# battery_monitor_6803-2_Rev2.net
KiCad netlist of a schematic drawn in EAGLE
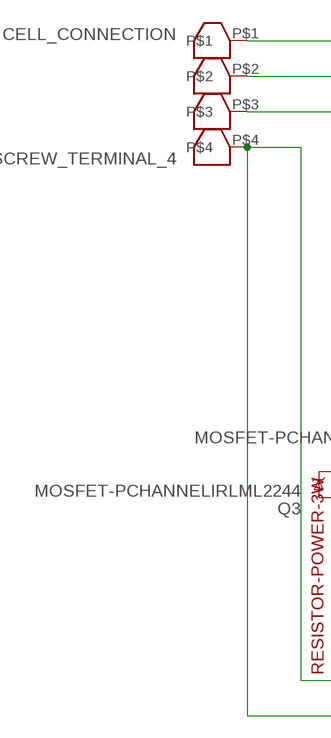
[diagram p0: schematic, sheet 1, part 1 of 2]
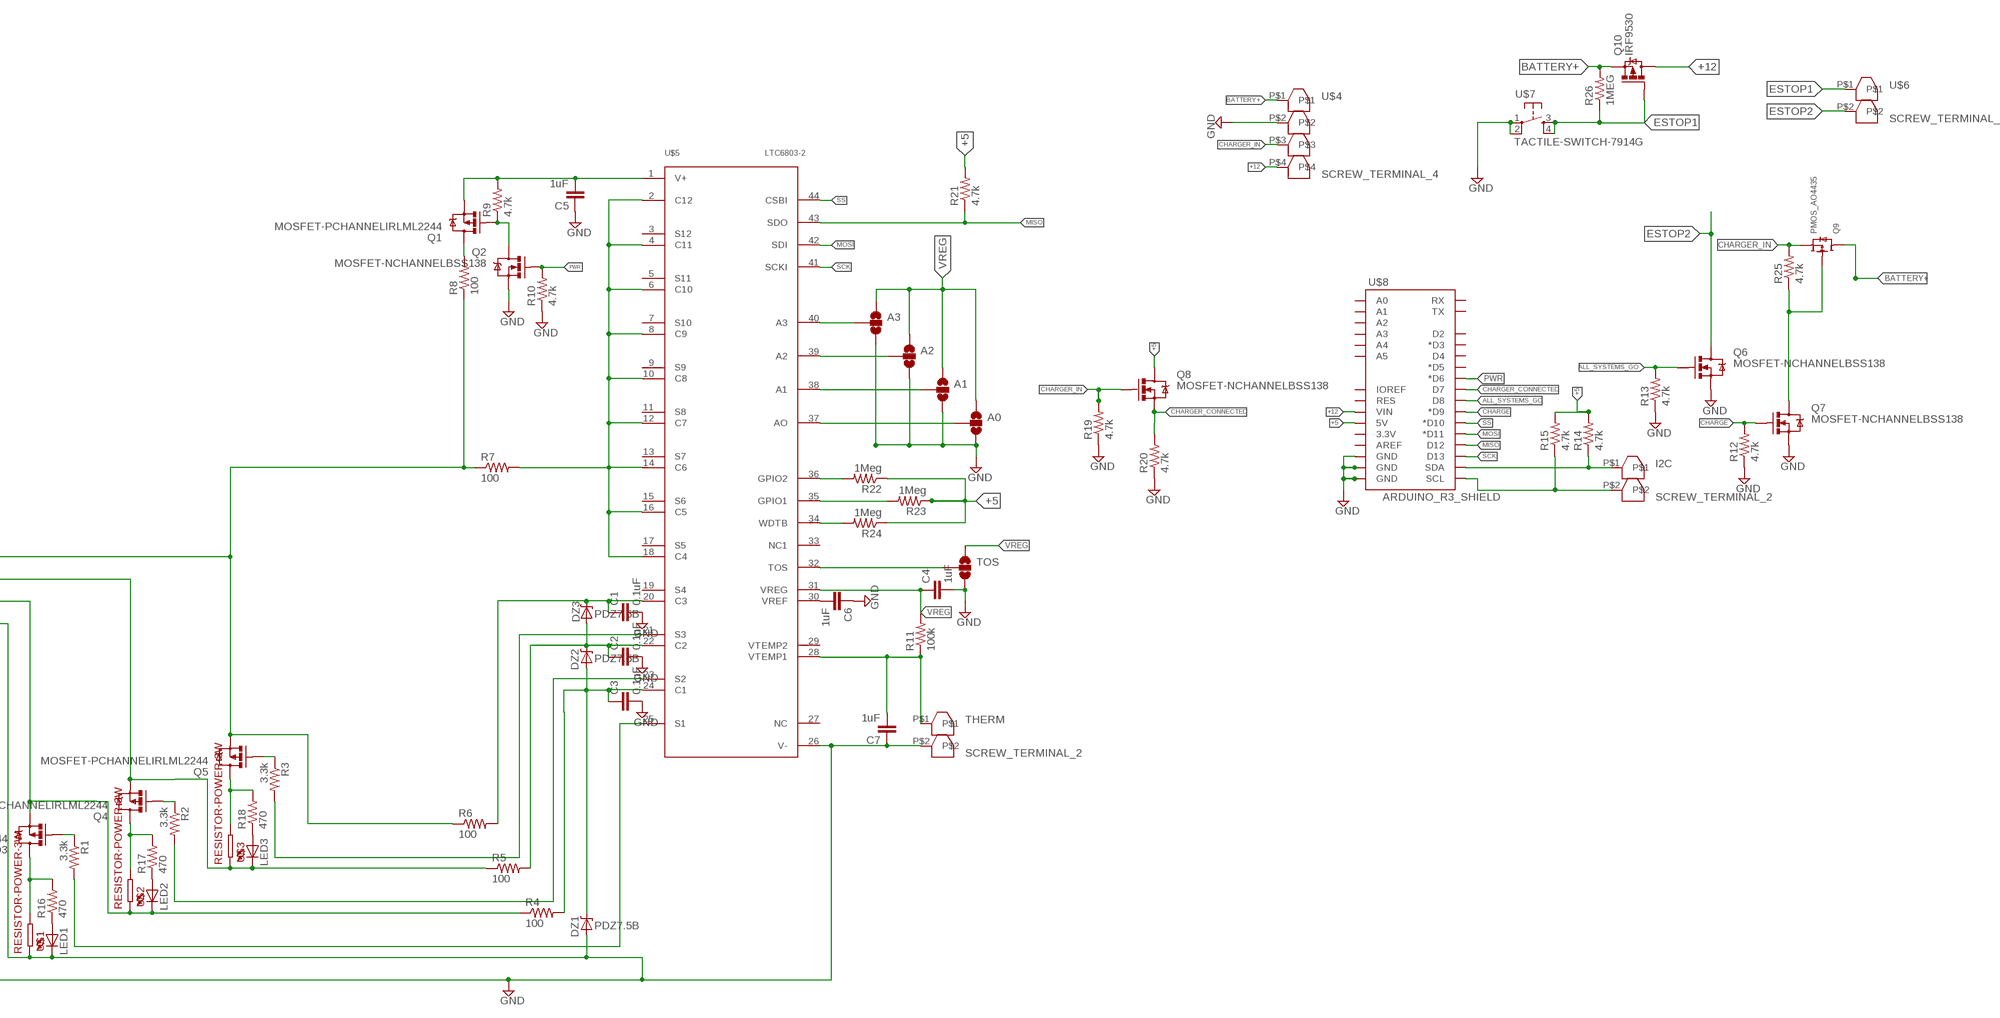
[diagram p1: schematic, sheet 1, part 2 of 2]

(export (version "E")
  (design (tool "Eeschema 10.0.6"))
  (components
    (comp (ref "A0")
      (value "SOLDERJUMPER_2WAYS")
      (footprint "eagle-import:SJ_3")
      (libsource (lib "eagle-import") (part "SOLDERJUMPER_2WAYS"))
    )
    (comp (ref "A1")
      (value "SOLDERJUMPER_2WAYS")
      (footprint "eagle-import:SJ_3")
      (libsource (lib "eagle-import") (part "SOLDERJUMPER_2WAYS"))
    )
    (comp (ref "A2")
      (value "SOLDERJUMPER_2WAYS")
      (footprint "eagle-import:SJ_3")
      (libsource (lib "eagle-import") (part "SOLDERJUMPER_2WAYS"))
    )
    (comp (ref "A3")
      (value "SOLDERJUMPER_2WAYS")
      (footprint "eagle-import:SJ_3")
      (libsource (lib "eagle-import") (part "SOLDERJUMPER_2WAYS"))
    )
    (comp (ref "C1")
      (value "0.1uF")
      (footprint "eagle-import:0603-CAP")
      (fields (field (name "MF") "AVX CORPORATION") (field (name "MPN") "0603YG104ZAT2A"))
      (libsource (lib "eagle-import") (part "0.1UF-100V-10%(0603)"))
    )
    (comp (ref "C2")
      (value "0.1uF")
      (footprint "eagle-import:0603-CAP")
      (fields (field (name "MF") "AVX CORPORATION") (field (name "MPN") "0603YG104ZAT2A"))
      (libsource (lib "eagle-import") (part "0.1UF-100V-10%(0603)"))
    )
    (comp (ref "C3")
      (value "0.1uF")
      (footprint "eagle-import:0603-CAP")
      (fields (field (name "MF") "AVX CORPORATION") (field (name "MPN") "0603YG104ZAT2A"))
      (libsource (lib "eagle-import") (part "0.1UF-100V-10%(0603)"))
    )
    (comp (ref "C4")
      (value "1uF")
      (footprint "eagle-import:0603-CAP")
      (fields (field (name "MPN") "C0603X5R0J105M030BC") (field (name "PROD_ID") "CAP-08390"))
      (libsource (lib "eagle-import") (part "0.1UF-100V-10%(0603)"))
    )
    (comp (ref "C5")
      (value "1uF")
      (footprint "eagle-import:0603-CAP")
      (fields (field (name "MPN") "C0603X5R0J105M030BC") (field (name "PROD_ID") "CAP-08390"))
      (libsource (lib "eagle-import") (part "0.1UF-100V-10%(0603)"))
    )
    (comp (ref "C6")
      (value "1uF")
      (footprint "eagle-import:0603-CAP")
      (fields (field (name "MPN") "C0603X5R0J105M030BC") (field (name "PROD_ID") "CAP-08390"))
      (libsource (lib "eagle-import") (part "0.1UF-100V-10%(0603)"))
    )
    (comp (ref "C7")
      (value "1uF")
      (footprint "eagle-import:0603-CAP")
      (fields (field (name "MPN") "C0603X5R0J105M030BC") (field (name "PROD_ID") "CAP-08390"))
      (libsource (lib "eagle-import") (part "0.1UF-100V-10%(0603)"))
    )
    (comp (ref "CELL_CONNECTION")
      (value "SCREW_TERMINAL_4")
      (footprint "eagle-import:SCREW_TERMINAL_4")
      (fields (field (name "MF") "TYCO ELECTRONICS") (field (name "MPN") "282834-4"))
      (libsource (lib "eagle-import") (part "SCREW_TERMINAL_4"))
    )
    (comp (ref "DZ1")
      (value "PDZ7.5B")
      (footprint "eagle-import:SOD-323")
      (fields (field (name "MPN") "PDZ7.5B,115"))
      (libsource (lib "eagle-import") (part "DIODE-ZENER-BZT52"))
    )
    (comp (ref "DZ2")
      (value "PDZ7.5B")
      (footprint "eagle-import:SOD-323")
      (fields (field (name "MPN") "PDZ7.5B,115"))
      (libsource (lib "eagle-import") (part "DIODE-ZENER-BZT52"))
    )
    (comp (ref "DZ3")
      (value "PDZ7.5B")
      (footprint "eagle-import:SOD-323")
      (fields (field (name "MPN") "PDZ7.5B,115"))
      (libsource (lib "eagle-import") (part "DIODE-ZENER-BZT52"))
    )
    (comp (ref "I2C")
      (value "SCREW_TERMINAL_2")
      (footprint "eagle-import:SCREW_TERMINAL_2")
      (fields (field (name "MF") "TYCO ELECTRONICS") (field (name "MPN") "282834-2"))
      (libsource (lib "eagle-import") (part "isaac1_SCREW_TERMINAL_2"))
    )
    (comp (ref "LED1")
      (value "LED0603")
      (footprint "eagle-import:LED-0603")
      (fields (field (name "MPN") "150060RS75000"))
      (libsource (lib "eagle-import") (part "LED0603"))
    )
    (comp (ref "LED2")
      (value "LED0603")
      (footprint "eagle-import:LED-0603")
      (fields (field (name "MPN") "150060RS75000"))
      (libsource (lib "eagle-import") (part "LED0603"))
    )
    (comp (ref "LED3")
      (value "LED0603")
      (footprint "eagle-import:LED-0603")
      (fields (field (name "MPN") "150060RS75000"))
      (libsource (lib "eagle-import") (part "LED0603"))
    )
    (comp (ref "Q1")
      (value "MOSFET-PCHANNELIRLML2244")
      (footprint "eagle-import:SOT23-3")
      (fields (field (name "MPN") "SI2369DS-T1-GE3"))
      (libsource (lib "eagle-import") (part "MOSFET-PCHANNELIRLML2244"))
    )
    (comp (ref "Q2")
      (value "MOSFET-NCHANNELBSS138")
      (footprint "eagle-import:SOT23")
      (fields (field (name "MPN") "IRLML0030TRPBF"))
      (libsource (lib "eagle-import") (part "MOSFET-NCHANNELBSS138"))
    )
    (comp (ref "Q3")
      (value "MOSFET-PCHANNELIRLML2244")
      (footprint "eagle-import:SOT23-3")
      (fields (field (name "MPN") "SI2369DS-T1-GE3"))
      (libsource (lib "eagle-import") (part "MOSFET-PCHANNELIRLML2244"))
    )
    (comp (ref "Q4")
      (value "MOSFET-PCHANNELIRLML2244")
      (footprint "eagle-import:SOT23-3")
      (fields (field (name "MPN") "SI2369DS-T1-GE3"))
      (libsource (lib "eagle-import") (part "MOSFET-PCHANNELIRLML2244"))
    )
    (comp (ref "Q5")
      (value "MOSFET-PCHANNELIRLML2244")
      (footprint "eagle-import:SOT23-3")
      (fields (field (name "MPN") "SI2369DS-T1-GE3"))
      (libsource (lib "eagle-import") (part "MOSFET-PCHANNELIRLML2244"))
    )
    (comp (ref "Q6")
      (value "MOSFET-NCHANNELBSS138")
      (footprint "eagle-import:SOT23")
      (fields (field (name "MPN") "IRLML0030TRPBF"))
      (libsource (lib "eagle-import") (part "MOSFET-NCHANNELBSS138"))
    )
    (comp (ref "Q7")
      (value "MOSFET-NCHANNELBSS138")
      (footprint "eagle-import:SOT23")
      (fields (field (name "MPN") "IRLML0030TRPBF"))
      (libsource (lib "eagle-import") (part "MOSFET-NCHANNELBSS138"))
    )
    (comp (ref "Q8")
      (value "MOSFET-NCHANNELBSS138")
      (footprint "eagle-import:SOT23")
      (fields (field (name "MPN") "IRLML0030TRPBF") (field (name "PROD_ID") "TRANS-00830"))
      (libsource (lib "eagle-import") (part "MOSFET-NCHANNELBSS138"))
    )
    (comp (ref "Q9")
      (value "PMOS_AO4435")
      (footprint "eagle-import:SOIC8")
      (fields (field (name "MPN") "SI9407BDY-T1-GE3"))
      (libsource (lib "eagle-import") (part "PMOS_AO4435"))
    )
    (comp (ref "Q10")
      (value "IRF9530")
      (footprint "eagle-import:TO220BV")
      (fields (field (name "MPN") "NTE2383"))
      (libsource (lib "eagle-import") (part "IRF9530"))
    )
    (comp (ref "R1")
      (value "3.3k")
      (footprint "eagle-import:0603-RES")
      (fields (field (name "MF") "VISHAY/DALE") (field (name "MPN") "CRCW06033K00FKEA"))
      (libsource (lib "eagle-import") (part "3.3KOHM1/10W1%(0603)"))
    )
    (comp (ref "R2")
      (value "3.3k")
      (footprint "eagle-import:0603-RES")
      (fields (field (name "MF") "VISHAY/DALE") (field (name "MPN") "CRCW06033K00FKEA"))
      (libsource (lib "eagle-import") (part "3.3KOHM1/10W1%(0603)"))
    )
    (comp (ref "R3")
      (value "3.3k")
      (footprint "eagle-import:0603-RES")
      (fields (field (name "MF") "VISHAY/DALE") (field (name "MPN") "CRCW06033K00FKEA"))
      (libsource (lib "eagle-import") (part "3.3KOHM1/10W1%(0603)"))
    )
    (comp (ref "R4")
      (value "100")
      (footprint "eagle-import:0603-RES")
      (fields (field (name "MPN") "ERJ-1GNF1000C"))
      (libsource (lib "eagle-import") (part "3.3KOHM1/10W1%(0603)"))
    )
    (comp (ref "R5")
      (value "100")
      (footprint "eagle-import:0603-RES")
      (fields (field (name "MPN") "ERJ-1GNF1000C"))
      (libsource (lib "eagle-import") (part "3.3KOHM1/10W1%(0603)"))
    )
    (comp (ref "R6")
      (value "100")
      (footprint "eagle-import:0603-RES")
      (fields (field (name "MPN") "ERJ-1GNF1000C"))
      (libsource (lib "eagle-import") (part "3.3KOHM1/10W1%(0603)"))
    )
    (comp (ref "R7")
      (value "100")
      (footprint "eagle-import:0603-RES")
      (fields (field (name "MPN") "ERJ-1GNF1000C"))
      (libsource (lib "eagle-import") (part "3.3KOHM1/10W1%(0603)"))
    )
    (comp (ref "R8")
      (value "100")
      (footprint "eagle-import:0603-RES")
      (fields (field (name "MPN") "ERJ-1GNF1000C"))
      (libsource (lib "eagle-import") (part "3.3KOHM1/10W1%(0603)"))
    )
    (comp (ref "R9")
      (value "4.7k")
      (footprint "eagle-import:0603-RES")
      (fields (field (name "MF") "VISHAY/DALE") (field (name "MPN") "CRCW06034K70FKEA"))
      (libsource (lib "eagle-import") (part "3.3KOHM1/10W1%(0603)"))
    )
    (comp (ref "R10")
      (value "4.7k")
      (footprint "eagle-import:0603-RES")
      (fields (field (name "MF") "VISHAY/DALE") (field (name "MPN") "CRCW06034K70FKEA"))
      (libsource (lib "eagle-import") (part "3.3KOHM1/10W1%(0603)"))
    )
    (comp (ref "R11")
      (value "100k")
      (footprint "eagle-import:0603-RES")
      (fields (field (name "MF") "FARNELL") (field (name "MPN") "MC0063W06035100K"))
      (libsource (lib "eagle-import") (part "3.3KOHM1/10W1%(0603)"))
    )
    (comp (ref "R12")
      (value "4.7k")
      (footprint "eagle-import:0603-RES")
      (fields (field (name "MF") "VISHAY/DALE") (field (name "MPN") "CRCW06034K70FKEA"))
      (libsource (lib "eagle-import") (part "3.3KOHM1/10W1%(0603)"))
    )
    (comp (ref "R13")
      (value "4.7k")
      (footprint "eagle-import:0603-RES")
      (fields (field (name "MF") "VISHAY/DALE") (field (name "MPN") "CRCW06034K70FKEA"))
      (libsource (lib "eagle-import") (part "3.3KOHM1/10W1%(0603)"))
    )
    (comp (ref "R14")
      (value "4.7k")
      (footprint "eagle-import:0603-RES")
      (fields (field (name "MF") "VISHAY/DALE") (field (name "MPN") "CRCW06034K70FKEA"))
      (libsource (lib "eagle-import") (part "3.3KOHM1/10W1%(0603)"))
    )
    (comp (ref "R15")
      (value "4.7k")
      (footprint "eagle-import:0603-RES")
      (fields (field (name "MF") "VISHAY/DALE") (field (name "MPN") "CRCW06034K70FKEA"))
      (libsource (lib "eagle-import") (part "3.3KOHM1/10W1%(0603)"))
    )
    (comp (ref "R16")
      (value "470")
      (footprint "eagle-import:0603-RES")
      (fields (field (name "MPN") "ERJ-P03F4700V") (field (name "PROD_ID") "RES-07851"))
      (libsource (lib "eagle-import") (part "3.3KOHM1/10W1%(0603)"))
    )
    (comp (ref "R17")
      (value "470")
      (footprint "eagle-import:0603-RES")
      (fields (field (name "MPN") "ERJ-P03F4700V") (field (name "PROD_ID") "RES-07851"))
      (libsource (lib "eagle-import") (part "3.3KOHM1/10W1%(0603)"))
    )
    (comp (ref "R18")
      (value "470")
      (footprint "eagle-import:0603-RES")
      (fields (field (name "MPN") "ERJ-P03F4700V") (field (name "PROD_ID") "RES-07851"))
      (libsource (lib "eagle-import") (part "3.3KOHM1/10W1%(0603)"))
    )
    (comp (ref "R19")
      (value "4.7k")
      (footprint "eagle-import:0603-RES")
      (fields
        (field (name "MF") "VISHAY/DALE")
        (field (name "MPN") "CRCW06034K70FKEA")
        (field (name "PROD_ID") "RES-07851")
      )
      (libsource (lib "eagle-import") (part "3.3KOHM1/10W1%(0603)"))
    )
    (comp (ref "R20")
      (value "4.7k")
      (footprint "eagle-import:0603-RES")
      (fields
        (field (name "MF") "VISHAY/DALE")
        (field (name "MPN") "CRCW06034K70FKEA")
        (field (name "PROD_ID") "RES-07851")
      )
      (libsource (lib "eagle-import") (part "3.3KOHM1/10W1%(0603)"))
    )
    (comp (ref "R21")
      (value "4.7k")
      (footprint "eagle-import:0603-RES")
      (fields
        (field (name "MF") "VISHAY/DALE")
        (field (name "MPN") "CRCW06034K70FKEA")
        (field (name "PROD_ID") "RES-07851")
      )
      (libsource (lib "eagle-import") (part "3.3KOHM1/10W1%(0603)"))
    )
    (comp (ref "R22")
      (value "1Meg")
      (footprint "eagle-import:0603-RES")
      (fields (field (name "MPN") "ERJ-3EKF1004V") (field (name "PROD_ID") "RES-07851"))
      (libsource (lib "eagle-import") (part "3.3KOHM1/10W1%(0603)"))
    )
    (comp (ref "R23")
      (value "1Meg")
      (footprint "eagle-import:0603-RES")
      (fields (field (name "MPN") "ERJ-3EKF1004V") (field (name "PROD_ID") "RES-07851"))
      (libsource (lib "eagle-import") (part "3.3KOHM1/10W1%(0603)"))
    )
    (comp (ref "R24")
      (value "1Meg")
      (footprint "eagle-import:0603-RES")
      (fields (field (name "MPN") "ERJ-3EKF1004V") (field (name "PROD_ID") "RES-07851"))
      (libsource (lib "eagle-import") (part "3.3KOHM1/10W1%(0603)"))
    )
    (comp (ref "R25")
      (value "4.7k")
      (footprint "eagle-import:0603-RES")
      (fields
        (field (name "MF") "VISHAY/DALE")
        (field (name "MPN") "CRCW06034K70FKEA")
        (field (name "PROD_ID") "RES-07851")
      )
      (libsource (lib "eagle-import") (part "3.3KOHM1/10W1%(0603)"))
    )
    (comp (ref "R26")
      (value "1MEG")
      (footprint "eagle-import:0603-RES")
      (fields (field (name "MPN") "ERJ-3EKF1004V"))
      (libsource (lib "eagle-import") (part "3.3KOHM1/10W1%(0603)"))
    )
    (comp (ref "THERM")
      (value "SCREW_TERMINAL_2")
      (footprint "eagle-import:SCREW_TERMINAL_2")
      (fields (field (name "MF") "TYCO ELECTRONICS") (field (name "MPN") "282834-2"))
      (libsource (lib "eagle-import") (part "isaac1_SCREW_TERMINAL_2"))
    )
    (comp (ref "TOS")
      (value "SOLDERJUMPER_2WAYS")
      (footprint "eagle-import:SJ_3")
      (libsource (lib "eagle-import") (part "SOLDERJUMPER_2WAYS"))
    )
    (comp (ref "U$1")
      (value "RESISTOR-POWER-3W")
      (footprint "eagle-import:RESISTOR-3W")
      (fields (field (name "MPN") "ERG-3SJ200"))
      (libsource (lib "eagle-import") (part "RESISTOR-POWER-3W"))
    )
    (comp (ref "U$2")
      (value "RESISTOR-POWER-3W")
      (footprint "eagle-import:RESISTOR-3W")
      (fields (field (name "MPN") "ERG-3SJ200"))
      (libsource (lib "eagle-import") (part "RESISTOR-POWER-3W"))
    )
    (comp (ref "U$3")
      (value "RESISTOR-POWER-3W")
      (footprint "eagle-import:RESISTOR-3W")
      (fields (field (name "MPN") "ERG-3SJ200"))
      (libsource (lib "eagle-import") (part "RESISTOR-POWER-3W"))
    )
    (comp (ref "U$4")
      (value "SCREW_TERMINAL_4")
      (footprint "eagle-import:SCREW_TERMINAL_4")
      (fields (field (name "MF") "TYCO ELECTRONICS") (field (name "MPN") "282834-4"))
      (libsource (lib "eagle-import") (part "SCREW_TERMINAL_4"))
    )
    (comp (ref "U$5")
      (value "LTC6803-2")
      (footprint "eagle-import:FSOP-44")
      (libsource (lib "eagle-import") (part "LTC6803-2"))
    )
    (comp (ref "U$6")
      (value "SCREW_TERMINAL_2")
      (footprint "eagle-import:SCREW_TERMINAL_2")
      (fields (field (name "MF") "TYCO ELECTRONICS") (field (name "MPN") "282834-2"))
      (libsource (lib "eagle-import") (part "SCREW_TERMINAL_2"))
    )
    (comp (ref "U$7")
      (value "TACTILE-SWITCH-7914G")
      (footprint "eagle-import:7914G")
      (fields (field (name "MF") "BOURNS, INC.") (field (name "MPN") "7914G-1-000E"))
      (libsource (lib "eagle-import") (part "TACTILE-SWITCH-7914G"))
    )
    (comp (ref "U$8")
      (value "ARDUINO_R3_SHIELD")
      (footprint "eagle-import:UNO_R3_SHIELD")
      (libsource (lib "eagle-import") (part "ARDUINO_R3_SHIELD"))
    )
  )
  (nets
    (net (code "1") (name "+5") (class "Default")
      (node (ref "Q8") (pin "3") (pinfunction "D_3") (pintype "passive"))
      (node (ref "R14") (pin "2") (pinfunction "2_2") (pintype "passive"))
      (node (ref "R15") (pin "2") (pinfunction "2_2") (pintype "passive"))
      (node (ref "R21") (pin "2") (pinfunction "2_2") (pintype "passive"))
      (node (ref "R22") (pin "1") (pinfunction "1_1") (pintype "passive"))
      (node (ref "R23") (pin "1") (pinfunction "1_1") (pintype "passive"))
      (node (ref "R24") (pin "1") (pinfunction "1_1") (pintype "passive"))
      (node (ref "U$8") (pin "5V") (pinfunction "5V_5V") (pintype "bidirectional"))
    )
    (net (code "2") (name "+12") (class "Default")
      (node (ref "Q10") (pin "D") (pinfunction "D_D") (pintype "passive"))
      (node (ref "U$4") (pin "P$4") (pinfunction "P$4_P$4") (pintype "bidirectional"))
      (node (ref "U$8") (pin "VIN") (pinfunction "VIN_VIN") (pintype "bidirectional"))
    )
    (net (code "3") (name "ALL_SYSTEMS_GO") (class "Default")
      (node (ref "Q6") (pin "1") (pinfunction "G_1") (pintype "passive"))
      (node (ref "R13") (pin "2") (pinfunction "2_2") (pintype "passive"))
      (node (ref "U$8") (pin "D8") (pinfunction "D8_D8") (pintype "bidirectional"))
    )
    (net (code "4") (name "BATTERY+") (class "Default")
      (node (ref "Q10") (pin "S") (pinfunction "S_S") (pintype "passive"))
      (node (ref "Q9") (pin "5") (pinfunction "DRAIN_5") (pintype "bidirectional"))
      (node (ref "Q9") (pin "6") (pinfunction "DRAIN_6") (pintype "bidirectional"))
      (node (ref "Q9") (pin "7") (pinfunction "DRAIN_7") (pintype "bidirectional"))
      (node (ref "Q9") (pin "8") (pinfunction "DRAIN_8") (pintype "bidirectional"))
      (node (ref "R26") (pin "2") (pinfunction "2_2") (pintype "passive"))
      (node (ref "U$4") (pin "P$1") (pinfunction "P$1_P$1") (pintype "bidirectional"))
    )
    (net (code "5") (name "CHARGE") (class "Default")
      (node (ref "Q7") (pin "1") (pinfunction "G_1") (pintype "passive"))
      (node (ref "R12") (pin "2") (pinfunction "2_2") (pintype "passive"))
      (node (ref "U$8") (pin "D9") (pinfunction "*D9_D9") (pintype "bidirectional"))
    )
    (net (code "6") (name "CHARGER_CONNECTED") (class "Default")
      (node (ref "Q8") (pin "2") (pinfunction "S_2") (pintype "passive"))
      (node (ref "R20") (pin "2") (pinfunction "2_2") (pintype "passive"))
      (node (ref "U$8") (pin "D7") (pinfunction "D7_D7") (pintype "bidirectional"))
    )
    (net (code "7") (name "CHARGER_IN") (class "Default")
      (node (ref "Q8") (pin "1") (pinfunction "G_1") (pintype "passive"))
      (node (ref "Q9") (pin "1") (pinfunction "SOURCE_1") (pintype "bidirectional"))
      (node (ref "Q9") (pin "2") (pinfunction "SOURCE_2") (pintype "bidirectional"))
      (node (ref "Q9") (pin "3") (pinfunction "SOURCE_3") (pintype "bidirectional"))
      (node (ref "R19") (pin "2") (pinfunction "2_2") (pintype "passive"))
      (node (ref "R25") (pin "2") (pinfunction "2_2") (pintype "passive"))
      (node (ref "U$4") (pin "P$3") (pinfunction "P$3_P$3") (pintype "bidirectional"))
    )
    (net (code "8") (name "ESTOP1") (class "Default")
      (node (ref "Q10") (pin "G") (pinfunction "G_G") (pintype "passive"))
      (node (ref "R26") (pin "1") (pinfunction "1_1") (pintype "passive"))
      (node (ref "U$6") (pin "P$1") (pinfunction "P$1_P$1") (pintype "bidirectional"))
      (node (ref "U$7") (pin "3") (pinfunction "3_3") (pintype "passive"))
      (node (ref "U$7") (pin "4") (pinfunction "4_4") (pintype "passive"))
    )
    (net (code "9") (name "ESTOP2") (class "Default")
      (node (ref "Q6") (pin "3") (pinfunction "D_3") (pintype "passive"))
      (node (ref "U$6") (pin "P$2") (pinfunction "P$2_P$2") (pintype "bidirectional"))
    )
    (net (code "10") (name "GND") (class "Default")
      (node (ref "A0") (pin "3") (pinfunction "3_3") (pintype "passive"))
      (node (ref "A1") (pin "3") (pinfunction "3_3") (pintype "passive"))
      (node (ref "A2") (pin "3") (pinfunction "3_3") (pintype "passive"))
      (node (ref "A3") (pin "3") (pinfunction "3_3") (pintype "passive"))
      (node (ref "C1") (pin "2") (pinfunction "2_2") (pintype "passive"))
      (node (ref "C2") (pin "2") (pinfunction "2_2") (pintype "passive"))
      (node (ref "C3") (pin "2") (pinfunction "2_2") (pintype "passive"))
      (node (ref "C4") (pin "2") (pinfunction "2_2") (pintype "passive"))
      (node (ref "C5") (pin "1") (pinfunction "1_1") (pintype "passive"))
      (node (ref "C6") (pin "1") (pinfunction "1_1") (pintype "passive"))
      (node (ref "C7") (pin "1") (pinfunction "1_1") (pintype "passive"))
      (node (ref "CELL_CONNECTION") (pin "P$4") (pinfunction "P$4_P$4") (pintype "bidirectional"))
      (node (ref "DZ1") (pin "2") (pinfunction "A_2") (pintype "passive"))
      (node (ref "LED1") (pin "C") (pinfunction "C_C") (pintype "passive"))
      (node (ref "Q2") (pin "2") (pinfunction "S_2") (pintype "passive"))
      (node (ref "Q6") (pin "2") (pinfunction "S_2") (pintype "passive"))
      (node (ref "Q7") (pin "2") (pinfunction "S_2") (pintype "passive"))
      (node (ref "R10") (pin "1") (pinfunction "1_1") (pintype "passive"))
      (node (ref "R12") (pin "1") (pinfunction "1_1") (pintype "passive"))
      (node (ref "R13") (pin "1") (pinfunction "1_1") (pintype "passive"))
      (node (ref "R19") (pin "1") (pinfunction "1_1") (pintype "passive"))
      (node (ref "R20") (pin "1") (pinfunction "1_1") (pintype "passive"))
      (node (ref "THERM") (pin "P$2") (pinfunction "P$2_P$2") (pintype "bidirectional"))
      (node (ref "TOS") (pin "3") (pinfunction "3_3") (pintype "passive"))
      (node (ref "U$1") (pin "P$2") (pinfunction "P$2_P$2") (pintype "bidirectional"))
      (node (ref "U$4") (pin "P$2") (pinfunction "P$2_P$2") (pintype "bidirectional"))
      (node (ref "U$5") (pin "26") (pinfunction "V-_26") (pintype "bidirectional"))
      (node (ref "U$7") (pin "1") (pinfunction "1_1") (pintype "passive"))
      (node (ref "U$7") (pin "2") (pinfunction "2_2") (pintype "passive"))
      (node (ref "U$8") (pin "GND@0") (pinfunction "GND_GND@0") (pintype "bidirectional"))
      (node (ref "U$8") (pin "GND@1") (pinfunction "GND_GND@1") (pintype "bidirectional"))
      (node (ref "U$8") (pin "GND@2") (pinfunction "GND_GND@2") (pintype "bidirectional"))
    )
    (net (code "11") (name "MISO") (class "Default")
      (node (ref "R21") (pin "1") (pinfunction "1_1") (pintype "passive"))
      (node (ref "U$5") (pin "43") (pinfunction "SDO_43") (pintype "bidirectional"))
      (node (ref "U$8") (pin "D12") (pinfunction "D12_D12") (pintype "bidirectional"))
    )
    (net (code "12") (name "MOSI") (class "Default")
      (node (ref "U$5") (pin "42") (pinfunction "SDI_42") (pintype "bidirectional"))
      (node (ref "U$8") (pin "D11") (pinfunction "*D11_D11") (pintype "bidirectional"))
    )
    (net (code "13") (name "Net-(DZ1-C)") (class "Default")
      (node (ref "C3") (pin "1") (pinfunction "1_1") (pintype "passive"))
      (node (ref "DZ1") (pin "1") (pinfunction "C_1") (pintype "passive"))
      (node (ref "DZ2") (pin "2") (pinfunction "A_2") (pintype "passive"))
      (node (ref "R4") (pin "2") (pinfunction "2_2") (pintype "passive"))
      (node (ref "U$5") (pin "24") (pinfunction "C1_24") (pintype "bidirectional"))
    )
    (net (code "14") (name "Net-(DZ2-C)") (class "Default")
      (node (ref "C2") (pin "1") (pinfunction "1_1") (pintype "passive"))
      (node (ref "DZ2") (pin "1") (pinfunction "C_1") (pintype "passive"))
      (node (ref "DZ3") (pin "2") (pinfunction "A_2") (pintype "passive"))
      (node (ref "R5") (pin "2") (pinfunction "2_2") (pintype "passive"))
      (node (ref "U$5") (pin "22") (pinfunction "C2_22") (pintype "bidirectional"))
    )
    (net (code "15") (name "Net-(DZ3-C)") (class "Default")
      (node (ref "C1") (pin "1") (pinfunction "1_1") (pintype "passive"))
      (node (ref "DZ3") (pin "1") (pinfunction "C_1") (pintype "passive"))
      (node (ref "R6") (pin "2") (pinfunction "2_2") (pintype "passive"))
      (node (ref "U$5") (pin "20") (pinfunction "C3_20") (pintype "bidirectional"))
    )
    (net (code "16") (name "Net-(I2C-PadP$1)") (class "Default")
      (node (ref "I2C") (pin "P$1") (pinfunction "P$1_P$1") (pintype "bidirectional"))
      (node (ref "R14") (pin "1") (pinfunction "1_1") (pintype "passive"))
      (node (ref "U$8") (pin "SDA") (pinfunction "SDA_SDA") (pintype "bidirectional"))
    )
    (net (code "17") (name "Net-(I2C-PadP$2)") (class "Default")
      (node (ref "I2C") (pin "P$2") (pinfunction "P$2_P$2") (pintype "bidirectional"))
      (node (ref "R15") (pin "1") (pinfunction "1_1") (pintype "passive"))
      (node (ref "U$8") (pin "SCL") (pinfunction "SCL_SCL") (pintype "bidirectional"))
    )
    (net (code "18") (name "Net-(LED1-PadA)") (class "Default")
      (node (ref "LED1") (pin "A") (pinfunction "A_A") (pintype "passive"))
      (node (ref "R16") (pin "1") (pinfunction "1_1") (pintype "passive"))
    )
    (net (code "19") (name "Net-(LED2-PadA)") (class "Default")
      (node (ref "LED2") (pin "A") (pinfunction "A_A") (pintype "passive"))
      (node (ref "R17") (pin "1") (pinfunction "1_1") (pintype "passive"))
    )
    (net (code "20") (name "Net-(LED3-PadA)") (class "Default")
      (node (ref "LED3") (pin "A") (pinfunction "A_A") (pintype "passive"))
      (node (ref "R18") (pin "1") (pinfunction "1_1") (pintype "passive"))
    )
    (net (code "21") (name "Net-(Q1-D)") (class "Default")
      (node (ref "Q1") (pin "3") (pinfunction "D_3") (pintype "passive"))
      (node (ref "R8") (pin "2") (pinfunction "2_2") (pintype "passive"))
    )
    (net (code "22") (name "Net-(Q1-G)") (class "Default")
      (node (ref "Q1") (pin "1") (pinfunction "G_1") (pintype "passive"))
      (node (ref "Q2") (pin "3") (pinfunction "D_3") (pintype "passive"))
      (node (ref "R9") (pin "1") (pinfunction "1_1") (pintype "passive"))
    )
    (net (code "23") (name "Net-(Q1-S)") (class "Default")
      (node (ref "C5") (pin "2") (pinfunction "2_2") (pintype "passive"))
      (node (ref "Q1") (pin "2") (pinfunction "S_2") (pintype "passive"))
      (node (ref "R9") (pin "2") (pinfunction "2_2") (pintype "passive"))
      (node (ref "U$5") (pin "1") (pinfunction "V+_1") (pintype "bidirectional"))
    )
    (net (code "24") (name "Net-(Q3-D)") (class "Default")
      (node (ref "Q3") (pin "3") (pinfunction "D_3") (pintype "passive"))
      (node (ref "R16") (pin "2") (pinfunction "2_2") (pintype "passive"))
      (node (ref "U$1") (pin "P$1") (pinfunction "P$1_P$1") (pintype "bidirectional"))
    )
    (net (code "25") (name "Net-(Q3-G)") (class "Default")
      (node (ref "Q3") (pin "1") (pinfunction "G_1") (pintype "passive"))
      (node (ref "R1") (pin "1") (pinfunction "1_1") (pintype "passive"))
    )
    (net (code "26") (name "Net-(Q3-S)") (class "Default")
      (node (ref "CELL_CONNECTION") (pin "P$3") (pinfunction "P$3_P$3") (pintype "bidirectional"))
      (node (ref "LED2") (pin "C") (pinfunction "C_C") (pintype "passive"))
      (node (ref "Q3") (pin "2") (pinfunction "S_2") (pintype "passive"))
      (node (ref "R4") (pin "1") (pinfunction "1_1") (pintype "passive"))
      (node (ref "U$2") (pin "P$2") (pinfunction "P$2_P$2") (pintype "bidirectional"))
    )
    (net (code "27") (name "Net-(Q4-D)") (class "Default")
      (node (ref "Q4") (pin "3") (pinfunction "D_3") (pintype "passive"))
      (node (ref "R17") (pin "2") (pinfunction "2_2") (pintype "passive"))
      (node (ref "U$2") (pin "P$1") (pinfunction "P$1_P$1") (pintype "bidirectional"))
    )
    (net (code "28") (name "Net-(Q4-G)") (class "Default")
      (node (ref "Q4") (pin "1") (pinfunction "G_1") (pintype "passive"))
      (node (ref "R2") (pin "1") (pinfunction "1_1") (pintype "passive"))
    )
    (net (code "29") (name "Net-(Q4-S)") (class "Default")
      (node (ref "CELL_CONNECTION") (pin "P$2") (pinfunction "P$2_P$2") (pintype "bidirectional"))
      (node (ref "LED3") (pin "C") (pinfunction "C_C") (pintype "passive"))
      (node (ref "Q4") (pin "2") (pinfunction "S_2") (pintype "passive"))
      (node (ref "R5") (pin "1") (pinfunction "1_1") (pintype "passive"))
      (node (ref "U$3") (pin "P$2") (pinfunction "P$2_P$2") (pintype "bidirectional"))
    )
    (net (code "30") (name "Net-(Q5-D)") (class "Default")
      (node (ref "Q5") (pin "3") (pinfunction "D_3") (pintype "passive"))
      (node (ref "R18") (pin "2") (pinfunction "2_2") (pintype "passive"))
      (node (ref "U$3") (pin "P$1") (pinfunction "P$1_P$1") (pintype "bidirectional"))
    )
    (net (code "31") (name "Net-(Q5-G)") (class "Default")
      (node (ref "Q5") (pin "1") (pinfunction "G_1") (pintype "passive"))
      (node (ref "R3") (pin "1") (pinfunction "1_1") (pintype "passive"))
    )
    (net (code "32") (name "Net-(Q5-S)") (class "Default")
      (node (ref "CELL_CONNECTION") (pin "P$1") (pinfunction "P$1_P$1") (pintype "bidirectional"))
      (node (ref "Q5") (pin "2") (pinfunction "S_2") (pintype "passive"))
      (node (ref "R6") (pin "1") (pinfunction "1_1") (pintype "passive"))
      (node (ref "R7") (pin "1") (pinfunction "1_1") (pintype "passive"))
      (node (ref "R8") (pin "1") (pinfunction "1_1") (pintype "passive"))
    )
    (net (code "33") (name "Net-(Q7-D)") (class "Default")
      (node (ref "Q7") (pin "3") (pinfunction "D_3") (pintype "passive"))
      (node (ref "Q9") (pin "4") (pinfunction "GATE_4") (pintype "bidirectional"))
      (node (ref "R25") (pin "1") (pinfunction "1_1") (pintype "passive"))
    )
    (net (code "34") (name "Net-(U$5-A1)") (class "Default")
      (node (ref "A1") (pin "2") (pinfunction "2_2") (pintype "passive"))
      (node (ref "U$5") (pin "38") (pinfunction "A1_38") (pintype "bidirectional"))
    )
    (net (code "35") (name "Net-(U$5-A2)") (class "Default")
      (node (ref "A2") (pin "2") (pinfunction "2_2") (pintype "passive"))
      (node (ref "U$5") (pin "39") (pinfunction "A2_39") (pintype "bidirectional"))
    )
    (net (code "36") (name "Net-(U$5-A3)") (class "Default")
      (node (ref "A3") (pin "2") (pinfunction "2_2") (pintype "passive"))
      (node (ref "U$5") (pin "40") (pinfunction "A3_40") (pintype "bidirectional"))
    )
    (net (code "37") (name "Net-(U$5-AO)") (class "Default")
      (node (ref "A0") (pin "2") (pinfunction "2_2") (pintype "passive"))
      (node (ref "U$5") (pin "37") (pinfunction "AO_37") (pintype "bidirectional"))
    )
    (net (code "38") (name "Net-(U$5-C10)") (class "Default")
      (node (ref "R7") (pin "2") (pinfunction "2_2") (pintype "passive"))
      (node (ref "U$5") (pin "10") (pinfunction "C8_10") (pintype "bidirectional"))
      (node (ref "U$5") (pin "12") (pinfunction "C7_12") (pintype "bidirectional"))
      (node (ref "U$5") (pin "14") (pinfunction "C6_14") (pintype "bidirectional"))
      (node (ref "U$5") (pin "16") (pinfunction "C5_16") (pintype "bidirectional"))
      (node (ref "U$5") (pin "18") (pinfunction "C4_18") (pintype "bidirectional"))
      (node (ref "U$5") (pin "2") (pinfunction "C12_2") (pintype "bidirectional"))
      (node (ref "U$5") (pin "4") (pinfunction "C11_4") (pintype "bidirectional"))
      (node (ref "U$5") (pin "6") (pinfunction "C10_6") (pintype "bidirectional"))
      (node (ref "U$5") (pin "8") (pinfunction "C9_8") (pintype "bidirectional"))
    )
    (net (code "39") (name "Net-(U$5-GPIO1)") (class "Default")
      (node (ref "R23") (pin "2") (pinfunction "2_2") (pintype "passive"))
      (node (ref "U$5") (pin "35") (pinfunction "GPIO1_35") (pintype "bidirectional"))
    )
    (net (code "40") (name "Net-(U$5-GPIO2)") (class "Default")
      (node (ref "R22") (pin "2") (pinfunction "2_2") (pintype "passive"))
      (node (ref "U$5") (pin "36") (pinfunction "GPIO2_36") (pintype "bidirectional"))
    )
    (net (code "41") (name "Net-(U$5-S1)") (class "Default")
      (node (ref "R1") (pin "2") (pinfunction "2_2") (pintype "passive"))
      (node (ref "U$5") (pin "25") (pinfunction "S1_25") (pintype "bidirectional"))
    )
    (net (code "42") (name "Net-(U$5-S2)") (class "Default")
      (node (ref "R2") (pin "2") (pinfunction "2_2") (pintype "passive"))
      (node (ref "U$5") (pin "23") (pinfunction "S2_23") (pintype "bidirectional"))
    )
    (net (code "43") (name "Net-(U$5-S3)") (class "Default")
      (node (ref "R3") (pin "2") (pinfunction "2_2") (pintype "passive"))
      (node (ref "U$5") (pin "21") (pinfunction "S3_21") (pintype "bidirectional"))
    )
    (net (code "44") (name "Net-(U$5-TOS)") (class "Default")
      (node (ref "TOS") (pin "2") (pinfunction "2_2") (pintype "passive"))
      (node (ref "U$5") (pin "32") (pinfunction "TOS_32") (pintype "bidirectional"))
    )
    (net (code "45") (name "Net-(U$5-VREF)") (class "Default")
      (node (ref "C6") (pin "2") (pinfunction "2_2") (pintype "passive"))
      (node (ref "U$5") (pin "30") (pinfunction "VREF_30") (pintype "bidirectional"))
    )
    (net (code "46") (name "Net-(U$5-VTEMP1)") (class "Default")
      (node (ref "C7") (pin "2") (pinfunction "2_2") (pintype "passive"))
      (node (ref "R11") (pin "1") (pinfunction "1_1") (pintype "passive"))
      (node (ref "THERM") (pin "P$1") (pinfunction "P$1_P$1") (pintype "bidirectional"))
      (node (ref "U$5") (pin "28") (pinfunction "VTEMP1_28") (pintype "bidirectional"))
    )
    (net (code "47") (name "Net-(U$5-WDTB)") (class "Default")
      (node (ref "R24") (pin "2") (pinfunction "2_2") (pintype "passive"))
      (node (ref "U$5") (pin "34") (pinfunction "WDTB_34") (pintype "bidirectional"))
    )
    (net (code "48") (name "PWR") (class "Default")
      (node (ref "Q2") (pin "1") (pinfunction "G_1") (pintype "passive"))
      (node (ref "R10") (pin "2") (pinfunction "2_2") (pintype "passive"))
      (node (ref "U$8") (pin "D6") (pinfunction "*D6_D6") (pintype "bidirectional"))
    )
    (net (code "49") (name "SCK") (class "Default")
      (node (ref "U$5") (pin "41") (pinfunction "SCKI_41") (pintype "bidirectional"))
      (node (ref "U$8") (pin "D13") (pinfunction "D13_D13") (pintype "bidirectional"))
    )
    (net (code "50") (name "SS") (class "Default")
      (node (ref "U$5") (pin "44") (pinfunction "CSBI_44") (pintype "bidirectional"))
      (node (ref "U$8") (pin "D10") (pinfunction "*D10_D10") (pintype "bidirectional"))
    )
    (net (code "51") (name "VREG") (class "Default")
      (node (ref "A0") (pin "1") (pinfunction "1_1") (pintype "passive"))
      (node (ref "A1") (pin "1") (pinfunction "1_1") (pintype "passive"))
      (node (ref "A2") (pin "1") (pinfunction "1_1") (pintype "passive"))
      (node (ref "A3") (pin "1") (pinfunction "1_1") (pintype "passive"))
      (node (ref "C4") (pin "1") (pinfunction "1_1") (pintype "passive"))
      (node (ref "R11") (pin "2") (pinfunction "2_2") (pintype "passive"))
      (node (ref "TOS") (pin "1") (pinfunction "1_1") (pintype "passive"))
      (node (ref "U$5") (pin "31") (pinfunction "VREG_31") (pintype "bidirectional"))
    )
    (net (code "52") (name "unconnected-(U$5-NC-Pad27)") (class "Default")
      (node (ref "U$5") (pin "27") (pinfunction "NC_27") (pintype "bidirectional"))
    )
    (net (code "53") (name "unconnected-(U$5-NC1-Pad33)") (class "Default")
      (node (ref "U$5") (pin "33") (pinfunction "NC1_33") (pintype "bidirectional"))
    )
    (net (code "54") (name "unconnected-(U$5-S4-Pad19)") (class "Default")
      (node (ref "U$5") (pin "19") (pinfunction "S4_19") (pintype "bidirectional"))
    )
    (net (code "55") (name "unconnected-(U$5-S5-Pad17)") (class "Default")
      (node (ref "U$5") (pin "17") (pinfunction "S5_17") (pintype "bidirectional"))
    )
    (net (code "56") (name "unconnected-(U$5-S6-Pad15)") (class "Default")
      (node (ref "U$5") (pin "15") (pinfunction "S6_15") (pintype "bidirectional"))
    )
    (net (code "57") (name "unconnected-(U$5-S7-Pad13)") (class "Default")
      (node (ref "U$5") (pin "13") (pinfunction "S7_13") (pintype "bidirectional"))
    )
    (net (code "58") (name "unconnected-(U$5-S8-Pad11)") (class "Default")
      (node (ref "U$5") (pin "11") (pinfunction "S8_11") (pintype "bidirectional"))
    )
    (net (code "59") (name "unconnected-(U$5-S9-Pad9)") (class "Default")
      (node (ref "U$5") (pin "9") (pinfunction "S9_9") (pintype "bidirectional"))
    )
    (net (code "60") (name "unconnected-(U$5-S10-Pad7)") (class "Default")
      (node (ref "U$5") (pin "7") (pinfunction "S10_7") (pintype "bidirectional"))
    )
    (net (code "61") (name "unconnected-(U$5-S11-Pad5)") (class "Default")
      (node (ref "U$5") (pin "5") (pinfunction "S11_5") (pintype "bidirectional"))
    )
    (net (code "62") (name "unconnected-(U$5-S12-Pad3)") (class "Default")
      (node (ref "U$5") (pin "3") (pinfunction "S12_3") (pintype "bidirectional"))
    )
    (net (code "63") (name "unconnected-(U$5-VTEMP2-Pad29)") (class "Default")
      (node (ref "U$5") (pin "29") (pinfunction "VTEMP2_29") (pintype "bidirectional"))
    )
    (net (code "64") (name "unconnected-(U$8-*D3-PadD3)") (class "Default")
      (node (ref "U$8") (pin "D3") (pinfunction "*D3_D3") (pintype "bidirectional"))
    )
    (net (code "65") (name "unconnected-(U$8-*D5-PadD5)") (class "Default")
      (node (ref "U$8") (pin "D5") (pinfunction "*D5_D5") (pintype "bidirectional"))
    )
    (net (code "66") (name "unconnected-(U$8-Pad3.3V)") (class "Default")
      (node (ref "U$8") (pin "3.3V") (pinfunction "3.3V_3.3V") (pintype "bidirectional"))
    )
    (net (code "67") (name "unconnected-(U$8-PadA0)") (class "Default")
      (node (ref "U$8") (pin "A0") (pinfunction "A0_A0") (pintype "bidirectional"))
    )
    (net (code "68") (name "unconnected-(U$8-PadA1)") (class "Default")
      (node (ref "U$8") (pin "A1") (pinfunction "A1_A1") (pintype "bidirectional"))
    )
    (net (code "69") (name "unconnected-(U$8-PadA2)") (class "Default")
      (node (ref "U$8") (pin "A2") (pinfunction "A2_A2") (pintype "bidirectional"))
    )
    (net (code "70") (name "unconnected-(U$8-PadA3)") (class "Default")
      (node (ref "U$8") (pin "A3") (pinfunction "A3_A3") (pintype "bidirectional"))
    )
    (net (code "71") (name "unconnected-(U$8-PadA4)") (class "Default")
      (node (ref "U$8") (pin "A4") (pinfunction "A4_A4") (pintype "bidirectional"))
    )
    (net (code "72") (name "unconnected-(U$8-PadA5)") (class "Default")
      (node (ref "U$8") (pin "A5") (pinfunction "A5_A5") (pintype "bidirectional"))
    )
    (net (code "73") (name "unconnected-(U$8-PadAREF)") (class "Default")
      (node (ref "U$8") (pin "AREF") (pinfunction "AREF_AREF") (pintype "bidirectional"))
    )
    (net (code "74") (name "unconnected-(U$8-PadD2)") (class "Default")
      (node (ref "U$8") (pin "D2") (pinfunction "D2_D2") (pintype "bidirectional"))
    )
    (net (code "75") (name "unconnected-(U$8-PadD4)") (class "Default")
      (node (ref "U$8") (pin "D4") (pinfunction "D4_D4") (pintype "bidirectional"))
    )
    (net (code "76") (name "unconnected-(U$8-PadIOREF)") (class "Default")
      (node (ref "U$8") (pin "IOREF") (pinfunction "IOREF_IOREF") (pintype "bidirectional"))
    )
    (net (code "77") (name "unconnected-(U$8-PadRES)") (class "Default")
      (node (ref "U$8") (pin "RES") (pinfunction "RES_RES") (pintype "bidirectional"))
    )
    (net (code "78") (name "unconnected-(U$8-PadRX)") (class "Default")
      (node (ref "U$8") (pin "RX") (pinfunction "RX_RX") (pintype "bidirectional"))
    )
    (net (code "79") (name "unconnected-(U$8-PadTX)") (class "Default")
      (node (ref "U$8") (pin "TX") (pinfunction "TX_TX") (pintype "bidirectional"))
    )
  )
)
